# schematic.net
KiCad netlist of a schematic drawn in Altium Designer
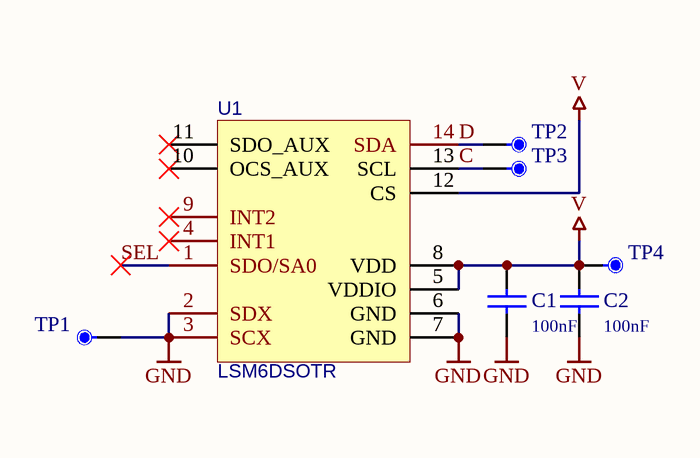
[diagram p0: schematic.SchDoc]

(export (version "E")
  (design (tool "Eeschema 10.0.6"))
  (components
    (comp (ref "C1")
      (value "100nF")
      (footprint "C0402")
      (fields (field (name "LCSC PART NUMBER") "C131394"))
      (libsource (lib "Miscellaneous Devices") (part "CAP"))
    )
    (comp (ref "C2")
      (value "100nF")
      (footprint "C0402")
      (fields (field (name "LCSC PART NUMBER") "C131394"))
      (libsource (lib "Miscellaneous Devices") (part "CAP"))
    )
    (comp (ref "TP1")
      (value "~")
      (footprint "TP2030_SMD")
      (libsource (lib "Miscellaneous Devices") (part "TP_Dup1"))
    )
    (comp (ref "TP2")
      (value "~")
      (footprint "TP2030_SMD")
      (libsource (lib "Miscellaneous Devices") (part "TP_Dup1"))
    )
    (comp (ref "TP3")
      (value "~")
      (footprint "TP2030_SMD")
      (libsource (lib "Miscellaneous Devices") (part "TP_Dup1"))
    )
    (comp (ref "TP4")
      (value "~")
      (footprint "TP2030_SMD")
      (libsource (lib "Miscellaneous Devices") (part "TP_Dup1"))
    )
    (comp (ref "U1")
      (value "LSM6DSOTR")
      (footprint "LGA-14_L3.0-W2.5-P0.50-TL")
      (fields (field (name "LCSC PART NUMBER") "C2655100"))
      (libsource (lib "Schlib1") (part "LSM6DSOTR"))
    )
  )
  (nets
    (net (code "1") (name "/C") (class "Default")
      (node (ref "TP3") (pin "1") (pinfunction "1_1") (pintype "passive"))
      (node (ref "U1") (pin "13") (pinfunction "SCL_13") (pintype "passive"))
    )
    (net (code "2") (name "/D") (class "Default")
      (node (ref "TP2") (pin "1") (pinfunction "1_1") (pintype "passive"))
      (node (ref "U1") (pin "14") (pinfunction "SDA_14") (pintype "passive"))
    )
    (net (code "3") (name "/SEL") (class "Default")
      (node (ref "U1") (pin "1") (pinfunction "SDO/SA0_1") (pintype "passive+no_connect"))
    )
    (net (code "4") (name "GND") (class "Default")
      (node (ref "C1") (pin "1") (pinfunction "1_1") (pintype "passive"))
      (node (ref "C2") (pin "1") (pinfunction "1_1") (pintype "passive"))
      (node (ref "TP1") (pin "1") (pinfunction "1_1") (pintype "passive"))
      (node (ref "U1") (pin "2") (pinfunction "SDX_2") (pintype "passive"))
      (node (ref "U1") (pin "3") (pinfunction "SCX_3") (pintype "passive"))
      (node (ref "U1") (pin "6") (pinfunction "GND_6") (pintype "passive"))
      (node (ref "U1") (pin "7") (pinfunction "GND_7") (pintype "passive"))
    )
    (net (code "5") (name "V") (class "Default")
      (node (ref "C1") (pin "2") (pinfunction "2_2") (pintype "passive"))
      (node (ref "C2") (pin "2") (pinfunction "2_2") (pintype "passive"))
      (node (ref "TP4") (pin "1") (pinfunction "1_1") (pintype "passive"))
      (node (ref "U1") (pin "12") (pinfunction "CS_12") (pintype "passive"))
      (node (ref "U1") (pin "5") (pinfunction "VDDIO_5") (pintype "passive"))
      (node (ref "U1") (pin "8") (pinfunction "VDD_8") (pintype "passive"))
    )
    (net (code "6") (name "unconnected-(U1-INT1-Pad4)") (class "Default")
      (node (ref "U1") (pin "4") (pinfunction "INT1_4") (pintype "passive+no_connect"))
    )
    (net (code "7") (name "unconnected-(U1-INT2-Pad9)") (class "Default")
      (node (ref "U1") (pin "9") (pinfunction "INT2_9") (pintype "passive+no_connect"))
    )
    (net (code "8") (name "unconnected-(U1-OCS_AUX-Pad10)") (class "Default")
      (node (ref "U1") (pin "10") (pinfunction "OCS_AUX_10") (pintype "passive+no_connect"))
    )
    (net (code "9") (name "unconnected-(U1-SDO_AUX-Pad11)") (class "Default")
      (node (ref "U1") (pin "11") (pinfunction "SDO_AUX_11") (pintype "passive+no_connect"))
    )
  )
)
